# Power_Dist_RCS.net
KiCad netlist of a schematic drawn in EAGLE
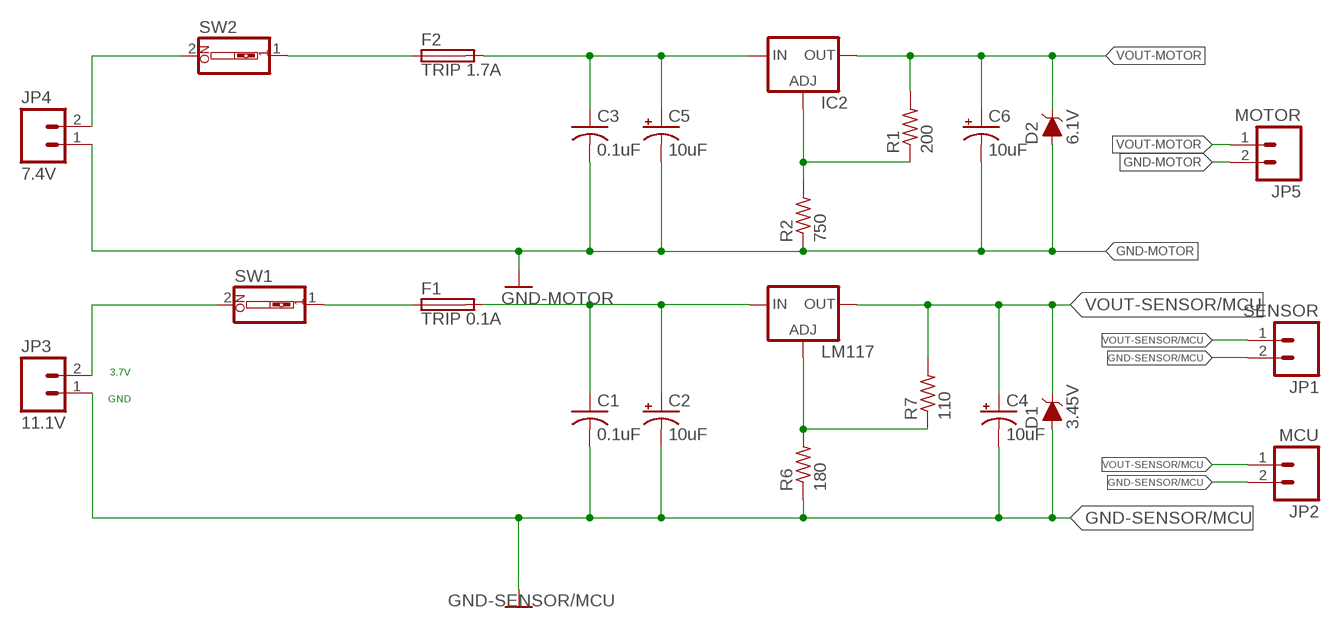
[diagram p0: schematic, sheet 1]

(export (version "E")
  (design (tool "Eeschema 10.0.6"))
  (components
    (comp (ref "C1")
      (value "0.1uF")
      (footprint "eagle-import:C1206")
      (libsource (lib "eagle-import") (part "C-USC1206"))
    )
    (comp (ref "C2")
      (value "10uF")
      (footprint "eagle-import:EIA3216")
      (libsource (lib "eagle-import") (part "10UF-POLAR-EIA3216-16V-10%(TANT)"))
    )
    (comp (ref "C3")
      (value "0.1uF")
      (footprint "eagle-import:C1206")
      (libsource (lib "eagle-import") (part "C-USC1206"))
    )
    (comp (ref "C4")
      (value "10uF")
      (footprint "eagle-import:EIA3216")
      (libsource (lib "eagle-import") (part "10UF-POLAR-EIA3216-16V-10%(TANT)"))
    )
    (comp (ref "C5")
      (value "10uF")
      (footprint "eagle-import:EIA3216")
      (libsource (lib "eagle-import") (part "10UF-POLAR-EIA3216-16V-10%(TANT)"))
    )
    (comp (ref "C6")
      (value "10uF")
      (footprint "eagle-import:EIA3216")
      (libsource (lib "eagle-import") (part "10UF-POLAR-EIA3216-16V-10%(TANT)"))
    )
    (comp (ref "D1")
      (value "3.45V")
      (footprint "eagle-import:SOD-323")
      (libsource (lib "eagle-import") (part "DIODE-ZENER-BZT52C3V6S"))
    )
    (comp (ref "D2")
      (value "6.1V")
      (footprint "eagle-import:SOD-323")
      (libsource (lib "eagle-import") (part "DIODE-ZENER-BZT52C3V6S"))
    )
    (comp (ref "F1")
      (value "TRIP 0.1A")
      (footprint "eagle-import:PICOFUSE")
      (libsource (lib "eagle-import") (part "PICOFUSE"))
    )
    (comp (ref "F2")
      (value "TRIP 1.7A")
      (footprint "eagle-import:PICOFUSE")
      (libsource (lib "eagle-import") (part "PICOFUSE"))
    )
    (comp (ref "IC2")
      (value "LM317-T039")
      (footprint "eagle-import:TO39-H03")
      (libsource (lib "eagle-import") (part "LM317-T039"))
    )
    (comp (ref "JP1")
      (value "SENSOR")
      (footprint "eagle-import:1X02")
      (libsource (lib "eagle-import") (part "M02PTH"))
    )
    (comp (ref "JP2")
      (value "MCU")
      (footprint "eagle-import:1X02")
      (libsource (lib "eagle-import") (part "M02PTH"))
    )
    (comp (ref "JP3")
      (value "11.1V")
      (footprint "eagle-import:JST-2-PTH")
      (libsource (lib "eagle-import") (part "M02JST-PTH-2"))
    )
    (comp (ref "JP4")
      (value "7.4V")
      (footprint "eagle-import:JST-2-PTH")
      (libsource (lib "eagle-import") (part "M02JST-PTH-2"))
    )
    (comp (ref "JP5")
      (value "MOTOR")
      (footprint "eagle-import:1X02")
      (libsource (lib "eagle-import") (part "M02PTH"))
    )
    (comp (ref "LM117")
      (value "LM317-T039")
      (footprint "eagle-import:TO39-H03")
      (libsource (lib "eagle-import") (part "LM317-T039"))
    )
    (comp (ref "R1")
      (value "200")
      (footprint "eagle-import:M1206")
      (libsource (lib "eagle-import") (part "R-US_M1206"))
    )
    (comp (ref "R2")
      (value "750")
      (footprint "eagle-import:M1206")
      (libsource (lib "eagle-import") (part "R-US_M1206"))
    )
    (comp (ref "R6")
      (value "180")
      (footprint "eagle-import:M1206")
      (libsource (lib "eagle-import") (part "R-US_M1206"))
    )
    (comp (ref "R7")
      (value "110")
      (footprint "eagle-import:M1206")
      (libsource (lib "eagle-import") (part "R-US_M1206"))
    )
    (comp (ref "SW1")
      (value "SW_DIP-1")
      (footprint "eagle-import:EDG-01")
      (libsource (lib "eagle-import") (part "SW_DIP-1"))
    )
    (comp (ref "SW2")
      (value "SW_DIP-1")
      (footprint "eagle-import:EDG-01")
      (libsource (lib "eagle-import") (part "SW_DIP-1"))
    )
  )
  (nets
    (net (code "1") (name "GND-MOTOR") (class "Default")
      (node (ref "C3") (pin "2") (pinfunction "2_2") (pintype "passive"))
      (node (ref "C5") (pin "-") (pinfunction "-_-") (pintype "passive"))
      (node (ref "C6") (pin "-") (pinfunction "-_-") (pintype "passive"))
      (node (ref "D2") (pin "A") (pinfunction "A_A") (pintype "passive"))
      (node (ref "JP4") (pin "1") (pinfunction "1_1") (pintype "passive"))
      (node (ref "JP5") (pin "2") (pinfunction "2_2") (pintype "passive"))
      (node (ref "R2") (pin "1") (pinfunction "1_1") (pintype "passive"))
    )
    (net (code "2") (name "GND-SENSOR{slash}MCU") (class "Default")
      (node (ref "C1") (pin "2") (pinfunction "2_2") (pintype "passive"))
      (node (ref "C2") (pin "-") (pinfunction "-_-") (pintype "passive"))
      (node (ref "C4") (pin "-") (pinfunction "-_-") (pintype "passive"))
      (node (ref "D1") (pin "A") (pinfunction "A_A") (pintype "passive"))
      (node (ref "JP1") (pin "2") (pinfunction "2_2") (pintype "passive"))
      (node (ref "JP2") (pin "2") (pinfunction "2_2") (pintype "passive"))
      (node (ref "JP3") (pin "1") (pinfunction "1_1") (pintype "passive"))
      (node (ref "R6") (pin "1") (pinfunction "1_1") (pintype "passive"))
    )
    (net (code "3") (name "Net-(F1-Pad1)") (class "Default")
      (node (ref "F1") (pin "1") (pinfunction "1_1") (pintype "passive"))
      (node (ref "SW1") (pin "1") (pinfunction "1_1") (pintype "passive"))
    )
    (net (code "4") (name "Net-(F2-Pad1)") (class "Default")
      (node (ref "F2") (pin "1") (pinfunction "1_1") (pintype "passive"))
      (node (ref "SW2") (pin "1") (pinfunction "1_1") (pintype "passive"))
    )
    (net (code "5") (name "Net-(IC2-ADJ)") (class "Default")
      (node (ref "IC2") (pin "2") (pinfunction "ADJ_2") (pintype "input"))
      (node (ref "R1") (pin "1") (pinfunction "1_1") (pintype "passive"))
      (node (ref "R2") (pin "2") (pinfunction "2_2") (pintype "passive"))
    )
    (net (code "6") (name "Net-(IC2-IN)") (class "Default")
      (node (ref "C3") (pin "1") (pinfunction "1_1") (pintype "passive"))
      (node (ref "C5") (pin "+") (pinfunction "+_+") (pintype "passive"))
      (node (ref "F2") (pin "2") (pinfunction "2_2") (pintype "passive"))
      (node (ref "IC2") (pin "1") (pinfunction "IN_1") (pintype "input"))
    )
    (net (code "7") (name "Net-(JP3-Pad2)") (class "Default")
      (node (ref "JP3") (pin "2") (pinfunction "2_2") (pintype "passive"))
      (node (ref "SW1") (pin "2") (pinfunction "2_2") (pintype "passive"))
    )
    (net (code "8") (name "Net-(JP4-Pad2)") (class "Default")
      (node (ref "JP4") (pin "2") (pinfunction "2_2") (pintype "passive"))
      (node (ref "SW2") (pin "2") (pinfunction "2_2") (pintype "passive"))
    )
    (net (code "9") (name "Net-(LM117-ADJ)") (class "Default")
      (node (ref "LM117") (pin "2") (pinfunction "ADJ_2") (pintype "input"))
      (node (ref "R6") (pin "2") (pinfunction "2_2") (pintype "passive"))
      (node (ref "R7") (pin "1") (pinfunction "1_1") (pintype "passive"))
    )
    (net (code "10") (name "Net-(LM117-IN)") (class "Default")
      (node (ref "C1") (pin "1") (pinfunction "1_1") (pintype "passive"))
      (node (ref "C2") (pin "+") (pinfunction "+_+") (pintype "passive"))
      (node (ref "F1") (pin "2") (pinfunction "2_2") (pintype "passive"))
      (node (ref "LM117") (pin "1") (pinfunction "IN_1") (pintype "input"))
    )
    (net (code "11") (name "VOUT-MOTOR") (class "Default")
      (node (ref "C6") (pin "+") (pinfunction "+_+") (pintype "passive"))
      (node (ref "D2") (pin "C") (pinfunction "C_C") (pintype "passive"))
      (node (ref "IC2") (pin "3") (pinfunction "OUT_3") (pintype "passive"))
      (node (ref "JP5") (pin "1") (pinfunction "1_1") (pintype "passive"))
      (node (ref "R1") (pin "2") (pinfunction "2_2") (pintype "passive"))
    )
    (net (code "12") (name "VOUT-SENSOR{slash}MCU") (class "Default")
      (node (ref "C4") (pin "+") (pinfunction "+_+") (pintype "passive"))
      (node (ref "D1") (pin "C") (pinfunction "C_C") (pintype "passive"))
      (node (ref "JP1") (pin "1") (pinfunction "1_1") (pintype "passive"))
      (node (ref "JP2") (pin "1") (pinfunction "1_1") (pintype "passive"))
      (node (ref "LM117") (pin "3") (pinfunction "OUT_3") (pintype "passive"))
      (node (ref "R7") (pin "2") (pinfunction "2_2") (pintype "passive"))
    )
  )
)
